# 3_6_1--esp32S3.net
KiCad netlist of a schematic drawn in EasyEDA Pro
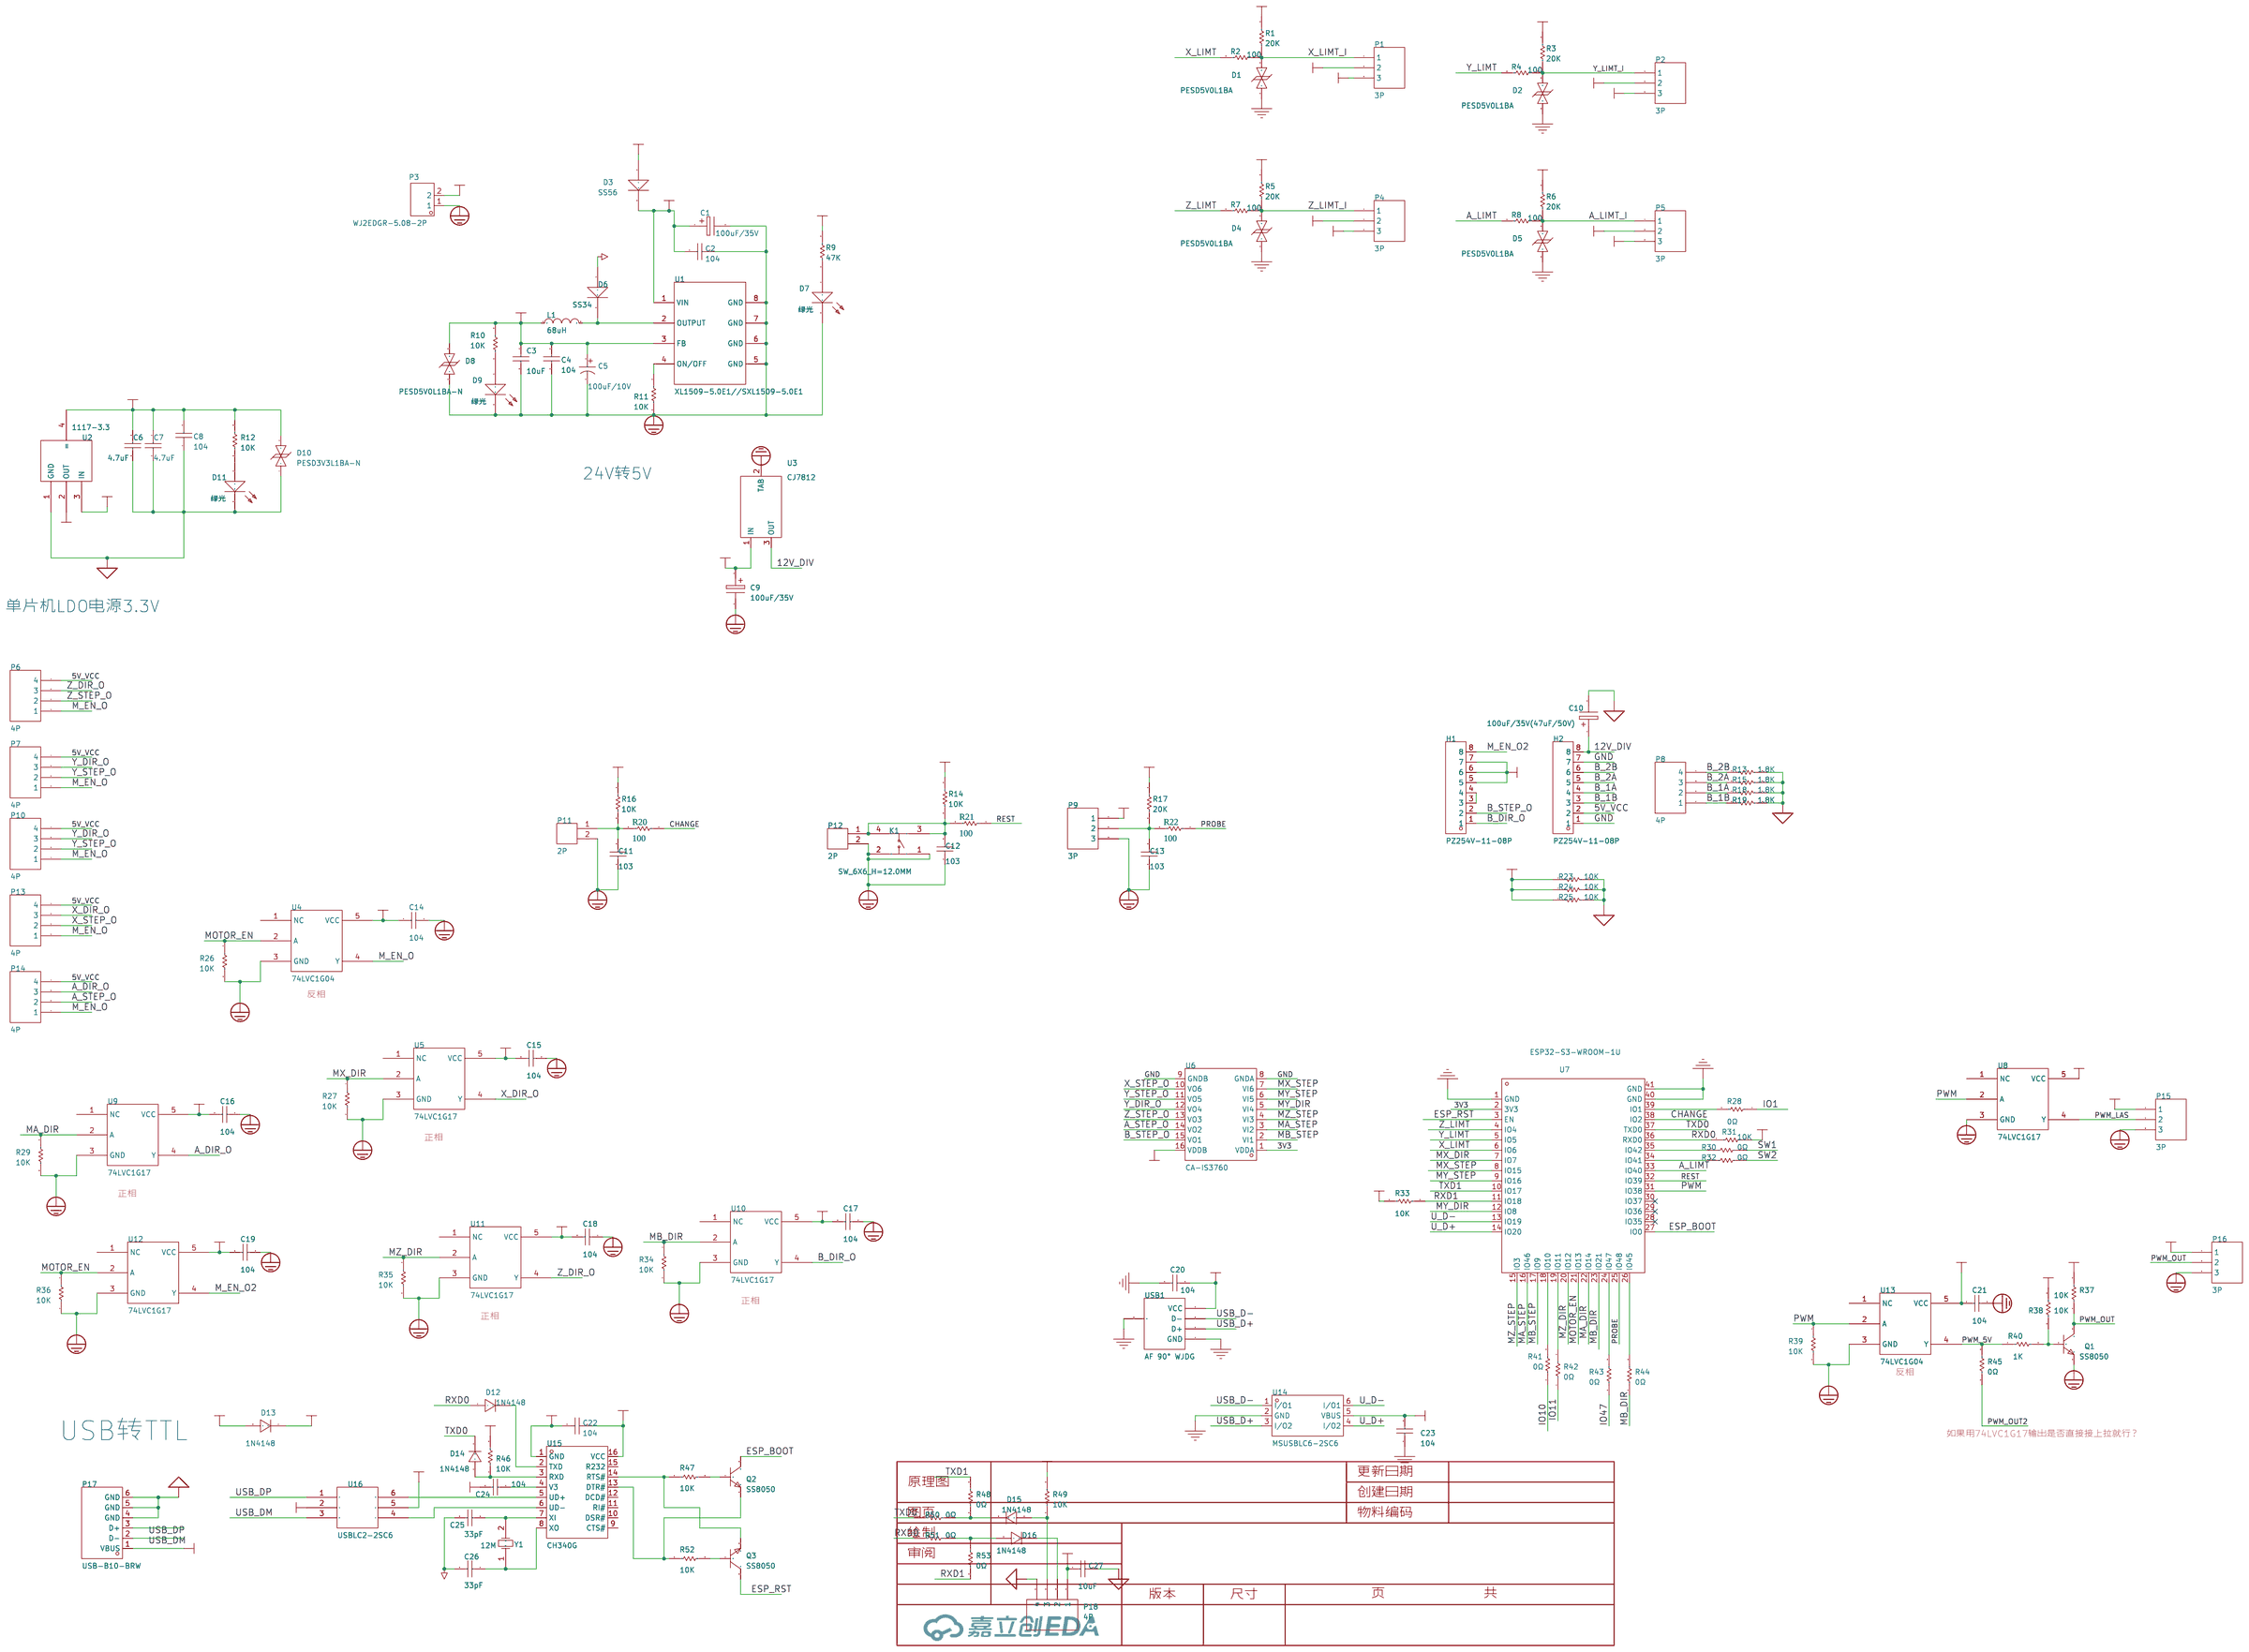
[diagram p0: schematic sheet]

(export (version "E")
  (design (tool "Eeschema 10.0.6"))
  (components
    (comp (ref "C1")
      (value "100uF/35V")
      (footprint "easyedapro:电解电容贴片10x10")
      (libsource (lib "easyedapro") (part "ELECTRO1"))
    )
    (comp (ref "C2")
      (value "104")
      (footprint "easyedapro:0603C")
      (description "Capacitor (Semiconductor SIM Model)")
      (libsource (lib "easyedapro") (part "Cap Semi"))
    )
    (comp (ref "C3") (value "10uF") (libsource (lib "") (part "CAP_1")))
    (comp (ref "C4")
      (value "104")
      (footprint "easyedapro:0603C")
      (description "Capacitor (Semiconductor SIM Model)")
      (libsource (lib "easyedapro") (part "Cap Semi"))
    )
    (comp (ref "C5")
      (value "100uF/10V")
      (footprint "easyedapro:CAP-SMD_BD5.0-L5.3-W5.3-RD")
      (fields (field (name "Manufacturer Part") "CS1A101M-CRD54") (field (name "Manufacturer") "ST(先科)"))
      (libsource (lib "easyedapro") (part "CS1A101M-CRD54"))
    )
    (comp (ref "C6") (value "4.7uF") (libsource (lib "") (part "CAP_1")))
    (comp (ref "C7") (value "4.7uF") (libsource (lib "") (part "CAP_1")))
    (comp (ref "C8")
      (value "104")
      (footprint "easyedapro:0603C")
      (description "Capacitor (Semiconductor SIM Model)")
      (libsource (lib "easyedapro") (part "Cap Semi"))
    )
    (comp (ref "C9")
      (value "100uF/35V")
      (footprint "easyedapro:电解电容贴片10x10")
      (libsource (lib "easyedapro") (part "ELECTRO1"))
    )
    (comp (ref "C10")
      (value "100uF/35V(47uF/50V)")
      (footprint "easyedapro:电解电容贴片10x10")
      (libsource (lib "easyedapro") (part "ELECTRO1"))
    )
    (comp (ref "C11") (value "103") (footprint "easyedapro:11") (libsource (lib "easyedapro") (part "CAP")))
    (comp (ref "C12") (value "103") (footprint "easyedapro:11") (libsource (lib "easyedapro") (part "CAP")))
    (comp (ref "C13") (value "103") (footprint "easyedapro:11") (libsource (lib "easyedapro") (part "CAP")))
    (comp (ref "C14")
      (value "104")
      (footprint "easyedapro:0603C")
      (description "Capacitor (Semiconductor SIM Model)")
      (libsource (lib "easyedapro") (part "Cap Semi"))
    )
    (comp (ref "C15")
      (value "104")
      (footprint "easyedapro:0603C")
      (description "Capacitor (Semiconductor SIM Model)")
      (libsource (lib "easyedapro") (part "Cap Semi"))
    )
    (comp (ref "C16")
      (value "104")
      (footprint "easyedapro:0603C")
      (description "Capacitor (Semiconductor SIM Model)")
      (libsource (lib "easyedapro") (part "Cap Semi"))
    )
    (comp (ref "C17")
      (value "104")
      (footprint "easyedapro:0603C")
      (description "Capacitor (Semiconductor SIM Model)")
      (libsource (lib "easyedapro") (part "Cap Semi"))
    )
    (comp (ref "C18")
      (value "104")
      (footprint "easyedapro:0603C")
      (description "Capacitor (Semiconductor SIM Model)")
      (libsource (lib "easyedapro") (part "Cap Semi"))
    )
    (comp (ref "C19")
      (value "104")
      (footprint "easyedapro:0603C")
      (description "Capacitor (Semiconductor SIM Model)")
      (libsource (lib "easyedapro") (part "Cap Semi"))
    )
    (comp (ref "C20")
      (value "104")
      (footprint "easyedapro:0603C")
      (description "Capacitor (Semiconductor SIM Model)")
      (libsource (lib "easyedapro") (part "Cap Semi"))
    )
    (comp (ref "C21")
      (value "104")
      (footprint "easyedapro:0603C")
      (description "Capacitor (Semiconductor SIM Model)")
      (libsource (lib "easyedapro") (part "Cap Semi"))
    )
    (comp (ref "C22")
      (value "104")
      (footprint "easyedapro:0603C")
      (description "Capacitor (Semiconductor SIM Model)")
      (libsource (lib "easyedapro") (part "Cap Semi"))
    )
    (comp (ref "C23")
      (value "104")
      (footprint "easyedapro:0603C")
      (description "Capacitor (Semiconductor SIM Model)")
      (libsource (lib "easyedapro") (part "Cap Semi"))
    )
    (comp (ref "C24")
      (value "104")
      (footprint "easyedapro:0603C")
      (description "Capacitor (Semiconductor SIM Model)")
      (libsource (lib "easyedapro") (part "Cap Semi"))
    )
    (comp (ref "C25")
      (value "18pF")
      (footprint "easyedapro:0603C")
      (description "Capacitor (Semiconductor SIM Model)")
      (libsource (lib "easyedapro") (part "Cap Semi"))
    )
    (comp (ref "C26")
      (value "18pF")
      (footprint "easyedapro:0603C")
      (description "Capacitor (Semiconductor SIM Model)")
      (libsource (lib "easyedapro") (part "Cap Semi"))
    )
    (comp (ref "C27") (value "10uF") (libsource (lib "") (part "CAP_1")))
    (comp (ref "D1")
      (value "PESD5V0L1BA")
      (footprint "easyedapro:SOD-523_L1.2-W0.8-LS1.6-BI")
      (description "极性:Bidirectional;反向关断电压（典型值）:5V (Max);击穿电压（最小值）:6V;箝位电压:15V;峰值脉冲电流（10/1000us）:5A (8/20us);")
      (fields (field (name "Manufacturer") "BORN伯恩半导体"))
      (libsource (lib "easyedapro") (part "PESD5V0S1BBN"))
    )
    (comp (ref "D2")
      (value "PESD5V0L1BA")
      (footprint "easyedapro:SOD-523_L1.2-W0.8-LS1.6-BI")
      (description "极性:Bidirectional;反向关断电压（典型值）:5V (Max);击穿电压（最小值）:6V;箝位电压:15V;峰值脉冲电流（10/1000us）:5A (8/20us);")
      (fields (field (name "Manufacturer") "BORN伯恩半导体"))
      (libsource (lib "easyedapro") (part "PESD5V0S1BBN"))
    )
    (comp (ref "D3") (value "SS56") (footprint "easyedapro:SMA") (libsource (lib "") (part "1N4148_1")))
    (comp (ref "D4")
      (value "PESD5V0L1BA")
      (footprint "easyedapro:SOD-523_L1.2-W0.8-LS1.6-BI")
      (description "极性:Bidirectional;反向关断电压（典型值）:5V (Max);击穿电压（最小值）:6V;箝位电压:15V;峰值脉冲电流（10/1000us）:5A (8/20us);")
      (fields (field (name "Manufacturer") "BORN伯恩半导体"))
      (libsource (lib "easyedapro") (part "PESD5V0S1BBN"))
    )
    (comp (ref "D5")
      (value "PESD5V0L1BA")
      (footprint "easyedapro:SOD-523_L1.2-W0.8-LS1.6-BI")
      (description "极性:Bidirectional;反向关断电压（典型值）:5V (Max);击穿电压（最小值）:6V;箝位电压:15V;峰值脉冲电流（10/1000us）:5A (8/20us);")
      (fields (field (name "Manufacturer") "BORN伯恩半导体"))
      (libsource (lib "easyedapro") (part "PESD5V0S1BBN"))
    )
    (comp (ref "D6") (value "SS34") (libsource (lib "easyedapro") (part "1N4148")))
    (comp (ref "D7")
      (value "绿光")
      (footprint "easyedapro:0603LED")
      (libsource (lib "easyedapro") (part "LED"))
    )
    (comp (ref "D8")
      (value "PESD5V0L1BA-N")
      (footprint "easyedapro:SOD-523_L1.2-W0.8-LS1.6-BI")
      (description "极性:Bidirectional;反向关断电压（典型值）:5V (Max);击穿电压（最小值）:6V;箝位电压:15V;峰值脉冲电流（10/1000us）:5A (8/20us);")
      (fields (field (name "Manufacturer") "BORN伯恩半导体"))
      (libsource (lib "easyedapro") (part "PESD5V0S1BBN"))
    )
    (comp (ref "D9")
      (value "绿光")
      (footprint "easyedapro:0603LED")
      (libsource (lib "easyedapro") (part "LED"))
    )
    (comp (ref "D10")
      (value "PESD3V3L1BA-N")
      (footprint "easyedapro:SOD-523_L1.2-W0.8-LS1.6-BI")
      (description "极性:Bidirectional;反向关断电压（典型值）:5V (Max);击穿电压（最小值）:6V;箝位电压:15V;峰值脉冲电流（10/1000us）:5A (8/20us);")
      (fields (field (name "Manufacturer") "BORN伯恩半导体"))
      (libsource (lib "easyedapro") (part "PESD5V0S1BBN"))
    )
    (comp (ref "D11")
      (value "绿光")
      (footprint "easyedapro:0603LED")
      (libsource (lib "easyedapro") (part "LED"))
    )
    (comp (ref "D12")
      (value "1N4148")
      (footprint "easyedapro:SOD-123_L2.8-W1.8-LS3.7-RD")
      (fields (field (name "Manufacturer") "MCC(美微科)"))
      (libsource (lib "easyedapro") (part "1N4148W-TP"))
    )
    (comp (ref "D13")
      (value "1N4148")
      (footprint "easyedapro:SOD-123_L2.8-W1.8-LS3.7-RD")
      (fields (field (name "Manufacturer") "MCC(美微科)"))
      (libsource (lib "easyedapro") (part "1N4148W-TP"))
    )
    (comp (ref "D14")
      (value "1N4148")
      (footprint "easyedapro:SOD-123_L2.8-W1.8-LS3.7-RD")
      (fields (field (name "Manufacturer") "MCC(美微科)"))
      (libsource (lib "easyedapro") (part "1N4148W-TP"))
    )
    (comp (ref "D15")
      (value "1N4148")
      (footprint "easyedapro:SOD-123_L2.8-W1.8-LS3.7-RD")
      (fields (field (name "Manufacturer") "MCC(美微科)"))
      (libsource (lib "easyedapro") (part "1N4148W-TP"))
    )
    (comp (ref "D16")
      (value "1N4148")
      (footprint "easyedapro:SOD-123_L2.8-W1.8-LS3.7-RD")
      (fields (field (name "Manufacturer") "MCC(美微科)"))
      (libsource (lib "easyedapro") (part "1N4148W-TP"))
    )
    (comp (ref "H1")
      (value "PZ254V-11-08P")
      (footprint "easyedapro:HDR-TH_8P-P2.54-V-M")
      (fields (field (name "Manufacturer") "XFCN(兴飞)"))
      (libsource (lib "easyedapro") (part "PZ254V-11-08P"))
    )
    (comp (ref "H2")
      (value "PZ254V-11-08P")
      (footprint "easyedapro:HDR-TH_8P-P2.54-V-M")
      (fields (field (name "Manufacturer") "XFCN(兴飞)"))
      (libsource (lib "easyedapro") (part "PZ254V-11-08P"))
    )
    (comp (ref "K1")
      (value "SW_6X6_H=12.0MM")
      (footprint "easyedapro:KEY-SMD_4P-L6.0-W6.0-P4.50-LS9.0")
      (libsource (lib "easyedapro") (part "SW_6X6_H=12.0MM"))
    )
    (comp (ref "L1")
      (value "68uH")
      (footprint "easyedapro:IND-SMD_L7.0-W7.0_SMDRI74-330MT")
      (description "电感值:33uH;精度:±20%;额定电流:960mA;饱和电流(Isat):1.8A;类型:屏蔽电感;")
      (fields (field (name "Manufacturer Part") "SMDRI74-330MT") (field (name "Manufacturer") "SXN(顺翔诺)"))
      (libsource (lib "easyedapro") (part "SMDRI74-330MT"))
    )
    (comp (ref "P1")
      (value "3P")
      (footprint "easyedapro:HDR1X3_CON")
      (libsource (lib "easyedapro") (part "3P"))
    )
    (comp (ref "P2")
      (value "3P")
      (footprint "easyedapro:HDR1X3_CON")
      (libsource (lib "easyedapro") (part "3P"))
    )
    (comp (ref "P3")
      (value "WJ2EDGR-5.08-2P")
      (footprint "easyedapro:CONN-TH_WJ2EDGR-5.08-2P")
      (description "每排PIN数:2;安装方式:弯针;排数:1;间距:5.08mm;连接器类型:板端/插座-开口;")
      (fields (field (name "Manufacturer") "KANGNEX(康奈克斯电气)"))
      (libsource (lib "easyedapro") (part "WJ2EDGR-5.08-2P"))
    )
    (comp (ref "P4")
      (value "3P")
      (footprint "easyedapro:HDR1X3_CON")
      (libsource (lib "easyedapro") (part "3P"))
    )
    (comp (ref "P5")
      (value "3P")
      (footprint "easyedapro:HDR1X3_CON")
      (libsource (lib "easyedapro") (part "3P"))
    )
    (comp (ref "P6")
      (value "4P")
      (footprint "easyedapro:HDR1X4_CON")
      (libsource (lib "easyedapro") (part "4P"))
    )
    (comp (ref "P7")
      (value "4P")
      (footprint "easyedapro:HDR1X4_CON")
      (libsource (lib "easyedapro") (part "4P"))
    )
    (comp (ref "P8")
      (value "4P")
      (footprint "easyedapro:HDR1X4_CON")
      (libsource (lib "easyedapro") (part "4P"))
    )
    (comp (ref "P9")
      (value "3P")
      (footprint "easyedapro:HDR1X3_CON")
      (libsource (lib "easyedapro") (part "3P"))
    )
    (comp (ref "P10")
      (value "4P")
      (footprint "easyedapro:HDR1X4_CON")
      (libsource (lib "easyedapro") (part "4P"))
    )
    (comp (ref "P11") (value "2P") (libsource (lib "easyedapro") (part "2P")))
    (comp (ref "P12") (value "2P") (libsource (lib "easyedapro") (part "2P")))
    (comp (ref "P13")
      (value "4P")
      (footprint "easyedapro:HDR1X4_CON")
      (libsource (lib "easyedapro") (part "4P"))
    )
    (comp (ref "P14")
      (value "4P")
      (footprint "easyedapro:HDR1X4_CON")
      (libsource (lib "easyedapro") (part "4P"))
    )
    (comp (ref "P15")
      (value "3P")
      (footprint "easyedapro:HDR1X3_CON")
      (libsource (lib "easyedapro") (part "3P"))
    )
    (comp (ref "P16")
      (value "3P")
      (footprint "easyedapro:HDR1X3_CON")
      (libsource (lib "easyedapro") (part "3P"))
    )
    (comp (ref "P17")
      (value "USB-B10-BRW")
      (footprint "easyedapro:USB-B-TH_USB-B10-BRW")
      (fields (field (name "Manufacturer") "XUNPU(讯普)"))
      (libsource (lib "easyedapro") (part "USB-B10-BRW"))
    )
    (comp (ref "P18")
      (value "4P")
      (footprint "easyedapro:HDR1X4_CON")
      (libsource (lib "easyedapro") (part "4P"))
    )
    (comp (ref "Q1")
      (value "SS8050")
      (footprint "easyedapro:SOT-23-3_L2.9-W1.3-P1.90-LS2.4-BR")
      (fields (field (name "Manufacturer") "CJ（江苏长电/长晶）"))
      (libsource (lib "easyedapro") (part "SS8050_C2150"))
    )
    (comp (ref "Q2")
      (value "SS8050")
      (footprint "easyedapro:SOT-23-3_L2.9-W1.3-P1.90-LS2.4-BR")
      (fields (field (name "Manufacturer") "Doeshare(德芯)"))
      (libsource (lib "easyedapro") (part "SS8050_C2931717"))
    )
    (comp (ref "Q3")
      (value "SS8050")
      (footprint "easyedapro:SOT-23-3_L2.9-W1.3-P1.90-LS2.4-BR")
      (fields (field (name "Manufacturer") "Doeshare(德芯)"))
      (libsource (lib "easyedapro") (part "SS8050_C2931717"))
    )
    (comp (ref "R1")
      (value "20K")
      (footprint "easyedapro:10")
      (description "Resistor")
      (libsource (lib "easyedapro") (part "RES"))
    )
    (comp (ref "R2")
      (value "100")
      (footprint "easyedapro:10")
      (description "Resistor")
      (libsource (lib "easyedapro") (part "RES"))
    )
    (comp (ref "R3")
      (value "20K")
      (footprint "easyedapro:10")
      (description "Resistor")
      (libsource (lib "easyedapro") (part "RES"))
    )
    (comp (ref "R4")
      (value "100")
      (footprint "easyedapro:10")
      (description "Resistor")
      (libsource (lib "easyedapro") (part "RES"))
    )
    (comp (ref "R5")
      (value "20K")
      (footprint "easyedapro:10")
      (description "Resistor")
      (libsource (lib "easyedapro") (part "RES"))
    )
    (comp (ref "R6")
      (value "20K")
      (footprint "easyedapro:10")
      (description "Resistor")
      (libsource (lib "easyedapro") (part "RES"))
    )
    (comp (ref "R7")
      (value "100")
      (footprint "easyedapro:10")
      (description "Resistor")
      (libsource (lib "easyedapro") (part "RES"))
    )
    (comp (ref "R8")
      (value "100")
      (footprint "easyedapro:10")
      (description "Resistor")
      (libsource (lib "easyedapro") (part "RES"))
    )
    (comp (ref "R9")
      (value "47K")
      (footprint "easyedapro:0603R")
      (description "Resistor")
      (libsource (lib "easyedapro") (part "RES"))
    )
    (comp (ref "R10")
      (value "10K")
      (footprint "easyedapro:0603R")
      (description "Resistor")
      (libsource (lib "easyedapro") (part "RES"))
    )
    (comp (ref "R11")
      (value "10K")
      (footprint "easyedapro:0603R")
      (description "Resistor")
      (libsource (lib "easyedapro") (part "RES"))
    )
    (comp (ref "R12")
      (value "10K")
      (footprint "easyedapro:0603R")
      (description "Resistor")
      (libsource (lib "easyedapro") (part "RES"))
    )
    (comp (ref "R13")
      (value "10K")
      (footprint "easyedapro:0603R")
      (description "Resistor")
      (libsource (lib "easyedapro") (part "10K"))
    )
    (comp (ref "R14")
      (value "10K")
      (footprint "easyedapro:0603R")
      (description "Resistor")
      (libsource (lib "easyedapro") (part "RES"))
    )
    (comp (ref "R15")
      (value "10K")
      (footprint "easyedapro:0603R")
      (description "Resistor")
      (libsource (lib "easyedapro") (part "10K"))
    )
    (comp (ref "R16")
      (value "10K")
      (footprint "easyedapro:0603R")
      (description "Resistor")
      (libsource (lib "easyedapro") (part "RES"))
    )
    (comp (ref "R17")
      (value "10K")
      (footprint "easyedapro:0603R")
      (description "Resistor")
      (libsource (lib "easyedapro") (part "RES"))
    )
    (comp (ref "R18")
      (value "10K")
      (footprint "easyedapro:0603R")
      (description "Resistor")
      (libsource (lib "easyedapro") (part "10K"))
    )
    (comp (ref "R19")
      (value "10K")
      (footprint "easyedapro:0603R")
      (description "Resistor")
      (libsource (lib "easyedapro") (part "10K"))
    )
    (comp (ref "R20")
      (value "100")
      (description "Resistor")
      (fields (field (name "Publisher") "Altium Limited"))
      (libsource (lib "") (part "RES_1"))
    )
    (comp (ref "R21")
      (value "100")
      (description "Resistor")
      (fields (field (name "Publisher") "Altium Limited"))
      (libsource (lib "") (part "RES_1"))
    )
    (comp (ref "R22")
      (value "100")
      (description "Resistor")
      (fields (field (name "Publisher") "Altium Limited"))
      (libsource (lib "") (part "RES_1"))
    )
    (comp (ref "R23")
      (value "10K")
      (footprint "easyedapro:0603R")
      (description "Resistor")
      (libsource (lib "easyedapro") (part "10K"))
    )
    (comp (ref "R24")
      (value "10K")
      (footprint "easyedapro:0603R")
      (description "Resistor")
      (libsource (lib "easyedapro") (part "10K"))
    )
    (comp (ref "R25")
      (value "10K")
      (footprint "easyedapro:0603R")
      (description "Resistor")
      (libsource (lib "easyedapro") (part "10K"))
    )
    (comp (ref "R26")
      (value "10K")
      (description "Resistor")
      (fields (field (name "Publisher") "Altium Limited"))
      (libsource (lib "") (part "RES_1"))
    )
    (comp (ref "R27")
      (value "10K")
      (description "Resistor")
      (fields (field (name "Publisher") "Altium Limited"))
      (libsource (lib "") (part "RES_1"))
    )
    (comp (ref "R28")
      (value "0Ω")
      (description "Resistor")
      (fields (field (name "Publisher") "Altium Limited"))
      (libsource (lib "") (part "RES_1"))
    )
    (comp (ref "R29")
      (value "10K")
      (description "Resistor")
      (fields (field (name "Publisher") "Altium Limited"))
      (libsource (lib "") (part "RES_1"))
    )
    (comp (ref "R30")
      (value "0Ω")
      (description "Resistor")
      (fields (field (name "Publisher") "Altium Limited"))
      (libsource (lib "") (part "RES_1"))
    )
    (comp (ref "R31")
      (value "10K")
      (footprint "easyedapro:0603R")
      (description "Resistor")
      (libsource (lib "easyedapro") (part "RES"))
    )
    (comp (ref "R32")
      (value "0Ω")
      (description "Resistor")
      (fields (field (name "Publisher") "Altium Limited"))
      (libsource (lib "") (part "RES_1"))
    )
    (comp (ref "R33")
      (value "10K")
      (footprint "easyedapro:0603R")
      (description "Resistor")
      (libsource (lib "easyedapro") (part "RES"))
    )
    (comp (ref "R34")
      (value "10K")
      (description "Resistor")
      (fields (field (name "Publisher") "Altium Limited"))
      (libsource (lib "") (part "RES_1"))
    )
    (comp (ref "R35")
      (value "10K")
      (description "Resistor")
      (fields (field (name "Publisher") "Altium Limited"))
      (libsource (lib "") (part "RES_1"))
    )
    (comp (ref "R36")
      (value "10K")
      (description "Resistor")
      (fields (field (name "Publisher") "Altium Limited"))
      (libsource (lib "") (part "RES_1"))
    )
    (comp (ref "R37")
      (value "10K")
      (description "Resistor")
      (fields (field (name "Publisher") "Altium Limited"))
      (libsource (lib "") (part "RES_1"))
    )
    (comp (ref "R38")
      (value "10K")
      (description "Resistor")
      (fields (field (name "Publisher") "Altium Limited"))
      (libsource (lib "") (part "RES_1"))
    )
    (comp (ref "R39")
      (value "10K")
      (description "Resistor")
      (fields (field (name "Publisher") "Altium Limited"))
      (libsource (lib "") (part "RES_1"))
    )
    (comp (ref "R40")
      (value "1K")
      (description "Resistor")
      (fields (field (name "Publisher") "Altium Limited"))
      (libsource (lib "") (part "RES_1"))
    )
    (comp (ref "R41")
      (value "0Ω")
      (description "Resistor")
      (fields (field (name "Publisher") "Altium Limited"))
      (libsource (lib "") (part "RES_1"))
    )
    (comp (ref "R42")
      (value "0Ω")
      (description "Resistor")
      (fields (field (name "Publisher") "Altium Limited"))
      (libsource (lib "") (part "RES_1"))
    )
    (comp (ref "R43")
      (value "0Ω")
      (description "Resistor")
      (fields (field (name "Publisher") "Altium Limited"))
      (libsource (lib "") (part "RES_1"))
    )
    (comp (ref "R44")
      (value "0Ω")
      (description "Resistor")
      (fields (field (name "Publisher") "Altium Limited"))
      (libsource (lib "") (part "RES_1"))
    )
    (comp (ref "R45")
      (value "0Ω")
      (description "Resistor")
      (fields (field (name "Publisher") "Altium Limited"))
      (libsource (lib "") (part "RES_1"))
    )
    (comp (ref "R46")
      (value "10K")
      (footprint "easyedapro:0603R")
      (description "Resistor")
      (libsource (lib "easyedapro") (part "RES"))
    )
    (comp (ref "R47")
      (value "10K")
      (footprint "easyedapro:0603R")
      (description "Resistor")
      (libsource (lib "easyedapro") (part "RES"))
    )
    (comp (ref "R48")
      (value "0Ω")
      (description "Resistor")
      (fields (field (name "Publisher") "Altium Limited"))
      (libsource (lib "") (part "RES_1"))
    )
    (comp (ref "R49")
      (value "10K")
      (footprint "easyedapro:0603R")
      (description "Resistor")
      (libsource (lib "easyedapro") (part "RES"))
    )
    (comp (ref "R50")
      (value "0Ω")
      (description "Resistor")
      (fields (field (name "Publisher") "Altium Limited"))
      (libsource (lib "") (part "RES_1"))
    )
    (comp (ref "R51")
      (value "0Ω")
      (description "Resistor")
      (fields (field (name "Publisher") "Altium Limited"))
      (libsource (lib "") (part "RES_1"))
    )
    (comp (ref "R52")
      (value "10K")
      (footprint "easyedapro:0603R")
      (description "Resistor")
      (libsource (lib "easyedapro") (part "RES"))
    )
    (comp (ref "R53")
      (value "0Ω")
      (description "Resistor")
      (fields (field (name "Publisher") "Altium Limited"))
      (libsource (lib "") (part "RES_1"))
    )
    (comp (ref "U1")
      (value "XL1509-5.0E1//SXL1509-5.0E1")
      (footprint "easyedapro:SOIC-8_L5.0-W4.0-P1.27-LS6.0-BL")
      (description "功能类型:降压型;同步整流:-;输出通道数:-;拓扑结构:-;输入电压:-;输出电流(最大值):-;开关频率:-;")
      (fields (field (name "Manufacturer") "XLSEMI(芯龙)"))
      (libsource (lib "easyedapro") (part "XL1509-5.0E1"))
    )
    (comp (ref "U2")
      (value "1117-3.3")
      (footprint "easyedapro:SOT-223")
      (libsource (lib "easyedapro") (part "LM1117"))
    )
    (comp (ref "U3")
      (value "CJ7812")
      (footprint "easyedapro:TO-263-2_L10.1-W9.1-P5.08-LS15.2-TL")
      (description "输出类型:固定;工作电压:35V;输出电压:12V;输出电流:1.5A;电源纹波抑制比(PSRR):71dB@(120Hz);输出极性:正极;")
      (fields (field (name "Manufacturer") "CJ(江苏长电/长晶)"))
      (libsource (lib "easyedapro") (part "CJ7812_C145151"))
    )
    (comp (ref "U4")
      (value "74LVC1G04")
      (footprint "easyedapro:SMD8")
      (libsource (lib "easyedapro") (part "74LVC1G04"))
    )
    (comp (ref "U5")
      (value "74LVC1G17")
      (footprint "easyedapro:SMD8")
      (libsource (lib "easyedapro") (part "74LVC1G04"))
    )
    (comp (ref "U6")
      (value "CA-IS3760")
      (footprint "easyedapro:SOIC-16_L9.9-W3.9-P1.27-LS6.0-BL")
      (fields (field (name "Manufacturer") "Chipanalog(川土微)"))
      (libsource (lib "easyedapro") (part "CA-IS3760HN"))
    )
    (comp (ref "U7")
      (value "ESP32-S3-WROOM-1U")
      (footprint "easyedapro:ESP32-S3-WROOM-1U")
      (fields
        (field (name "Manufacturer Part") "ESP32-S3-WROOM-1(N16R2)")
        (field (name "Manufacturer") "ESPRESSIF(----)")
      )
      (libsource (lib "easyedapro") (part "ESP32-S3-WROOM-1(N16R2)"))
    )
    (comp (ref "U8")
      (value "74LVC1G17")
      (footprint "easyedapro:SMD8")
      (libsource (lib "easyedapro") (part "74LVC1G04"))
    )
    (comp (ref "U9")
      (value "74LVC1G17")
      (footprint "easyedapro:SMD8")
      (libsource (lib "easyedapro") (part "74LVC1G04"))
    )
    (comp (ref "U10")
      (value "74LVC1G17")
      (footprint "easyedapro:SMD8")
      (libsource (lib "easyedapro") (part "74LVC1G04"))
    )
    (comp (ref "U11")
      (value "74LVC1G17")
      (footprint "easyedapro:SMD8")
      (libsource (lib "easyedapro") (part "74LVC1G04"))
    )
    (comp (ref "U12")
      (value "74LVC1G17")
      (footprint "easyedapro:SMD8")
      (libsource (lib "easyedapro") (part "74LVC1G04"))
    )
    (comp (ref "U13")
      (value "74LVC1G04")
      (footprint "easyedapro:SMD8")
      (libsource (lib "easyedapro") (part "74LVC1G04"))
    )
    (comp (ref "U14")
      (value "MSUSBLC6-2SC6")
      (footprint "easyedapro:SOT-23-6_L2.9-W1.6-P0.95-LS2.8-BL")
      (description "反向截止电压(Vrwm):5V;最大钳位电压:15V;峰值脉冲电流(Ipp)@10/1000us:6A;峰值脉冲功率(Ppp)@10/1000us:150W;击穿电压:9V;")
      (fields (field (name "Manufacturer") "MSKSEMI(美森科)"))
      (libsource (lib "easyedapro") (part "MSUSBLC6-2SC6"))
    )
    (comp (ref "U15")
      (value "CH340G")
      (footprint "easyedapro:SOIC-16_L9.9-W3.9-P1.27-LS6.0-BL")
      (description "应用功能:收发器;接口协议:USB 2.0;数据速率:2Mbps;")
      (fields (field (name "Manufacturer") "WCH(南京沁恒)"))
      (libsource (lib "easyedapro") (part "CH340G"))
    )
    (comp (ref "U16")
      (value "USBLC2-2SC6")
      (footprint "easyedapro:SOT-23-6")
      (libsource (lib "easyedapro") (part "DIP6"))
    )
    (comp (ref "USB1")
      (value "AF 90° WJDG")
      (footprint "easyedapro:USB-A-TH_AF-WJDG")
      (description "连接器类型:Type-A;标准:USB 2.0;公母:母;安装方式:弯插;触点数量:4P;端口数量:1;额定电流 - 电源:1.5A;工作温度范围:-25°C~+85°C;")
      (fields (field (name "Manufacturer") "SHOU HAN(首韩)"))
      (libsource (lib "easyedapro") (part "AF 90° WJDG"))
    )
    (comp (ref "Y1")
      (value "12M")
      (footprint "easyedapro:晶振贴片49SSMD")
      (description "Crystal Oscillator")
      (libsource (lib "easyedapro") (part "XTAL"))
    )
  )
  (nets
    (net (code "1") (name "/12V_DIV") (class "Default")
      (node (ref "C10") (pin "1") (pintype "unspecified"))
      (node (ref "H2") (pin "8") (pinfunction "8_8") (pintype "unspecified"))
      (node (ref "U3") (pin "3") (pinfunction "OUT_3") (pintype "unspecified"))
    )
    (net (code "2") (name "/A_DIR_O") (class "Default")
      (node (ref "P14") (pin "3") (pinfunction "3_3") (pintype "unspecified"))
      (node (ref "U9") (pin "4") (pinfunction "Y_4") (pintype "unspecified"))
    )
    (net (code "3") (name "/A_LIMT") (class "Default")
      (node (ref "R8") (pin "2") (pinfunction "2_2") (pintype "unspecified"))
      (node (ref "U7") (pin "33") (pinfunction "IO40_33") (pintype "unspecified"))
    )
    (net (code "4") (name "/A_LIMT_I") (class "Default")
      (node (ref "D5") (pin "2") (pinfunction "2_2") (pintype "input"))
      (node (ref "P5") (pin "1") (pinfunction "1_1") (pintype "unspecified"))
      (node (ref "R6") (pin "1") (pinfunction "1_1") (pintype "unspecified"))
      (node (ref "R8") (pin "1") (pinfunction "1_1") (pintype "unspecified"))
    )
    (net (code "5") (name "/A_STEP_O") (class "Default")
      (node (ref "P14") (pin "2") (pinfunction "2_2") (pintype "unspecified"))
      (node (ref "U6") (pin "14") (pinfunction "VO2_14") (pintype "unspecified"))
    )
    (net (code "6") (name "/B_1A") (class "Default")
      (node (ref "H2") (pin "4") (pinfunction "4_4") (pintype "unspecified"))
      (node (ref "P8") (pin "2") (pinfunction "2_2") (pintype "unspecified"))
      (node (ref "R18") (pin "1") (pinfunction "1_1") (pintype "unspecified"))
    )
    (net (code "7") (name "/B_1B") (class "Default")
      (node (ref "H2") (pin "3") (pinfunction "3_3") (pintype "unspecified"))
      (node (ref "P8") (pin "1") (pinfunction "1_1") (pintype "unspecified"))
      (node (ref "R19") (pin "1") (pinfunction "1_1") (pintype "unspecified"))
    )
    (net (code "8") (name "/B_2A") (class "Default")
      (node (ref "H2") (pin "5") (pinfunction "5_5") (pintype "unspecified"))
      (node (ref "P8") (pin "3") (pinfunction "3_3") (pintype "unspecified"))
      (node (ref "R15") (pin "1") (pinfunction "1_1") (pintype "unspecified"))
    )
    (net (code "9") (name "/B_2B") (class "Default")
      (node (ref "H2") (pin "6") (pinfunction "6_6") (pintype "unspecified"))
      (node (ref "P8") (pin "4") (pinfunction "4_4") (pintype "unspecified"))
      (node (ref "R13") (pin "1") (pinfunction "1_1") (pintype "unspecified"))
    )
    (net (code "10") (name "/B_DIR_O") (class "Default")
      (node (ref "H1") (pin "1") (pinfunction "1_1") (pintype "unspecified"))
      (node (ref "U10") (pin "4") (pinfunction "Y_4") (pintype "unspecified"))
    )
    (net (code "11") (name "/B_STEP_O") (class "Default")
      (node (ref "H1") (pin "2") (pinfunction "2_2") (pintype "unspecified"))
      (node (ref "U6") (pin "15") (pinfunction "VO1_15") (pintype "unspecified"))
    )
    (net (code "12") (name "/CHANGE") (class "Default")
      (node (ref "R20") (pin "1") (pinfunction "1_1") (pintype "input"))
      (node (ref "U7") (pin "38") (pinfunction "IO2_38") (pintype "unspecified"))
    )
    (net (code "13") (name "/ESP_BOOT") (class "Default")
      (node (ref "Q2") (pin "3") (pinfunction "C_3") (pintype "unspecified"))
      (node (ref "U7") (pin "27") (pinfunction "IO0_27") (pintype "unspecified"))
    )
    (net (code "14") (name "/ESP_RST") (class "Default")
      (node (ref "Q3") (pin "3") (pinfunction "C_3") (pintype "unspecified"))
      (node (ref "U7") (pin "3") (pinfunction "EN_3") (pintype "unspecified"))
    )
    (net (code "15") (name "/IO1") (class "Default")
      (node (ref "R28") (pin "1") (pinfunction "1_1") (pintype "input"))
    )
    (net (code "16") (name "/IO10") (class "Default")
      (node (ref "R41") (pin "1") (pinfunction "1_1") (pintype "input"))
    )
    (net (code "17") (name "/IO11") (class "Default")
      (node (ref "R42") (pin "1") (pinfunction "1_1") (pintype "input"))
    )
    (net (code "18") (name "/IO47") (class "Default")
      (node (ref "R43") (pin "1") (pinfunction "1_1") (pintype "input"))
    )
    (net (code "19") (name "/MA_DIR") (class "Default")
      (node (ref "R29") (pin "1") (pinfunction "1_1") (pintype "input"))
      (node (ref "U7") (pin "22") (pinfunction "IO14_22") (pintype "unspecified"))
      (node (ref "U9") (pin "2") (pinfunction "A_2") (pintype "unspecified"))
    )
    (net (code "20") (name "/MA_STEP") (class "Default")
      (node (ref "U6") (pin "3") (pinfunction "VI2_3") (pintype "unspecified"))
      (node (ref "U7") (pin "16") (pinfunction "IO46_16") (pintype "unspecified"))
    )
    (net (code "21") (name "/MB_DIR") (class "Default")
      (node (ref "R34") (pin "1") (pinfunction "1_1") (pintype "input"))
      (node (ref "R44") (pin "1") (pinfunction "1_1") (pintype "input"))
      (node (ref "U10") (pin "2") (pinfunction "A_2") (pintype "unspecified"))
      (node (ref "U7") (pin "23") (pinfunction "IO21_23") (pintype "unspecified"))
    )
    (net (code "22") (name "/MB_STEP") (class "Default")
      (node (ref "U6") (pin "2") (pinfunction "VI1_2") (pintype "unspecified"))
      (node (ref "U7") (pin "17") (pinfunction "IO9_17") (pintype "unspecified"))
    )
    (net (code "23") (name "/MOTOR_EN") (class "Default")
      (node (ref "R26") (pin "1") (pinfunction "1_1") (pintype "input"))
      (node (ref "R36") (pin "1") (pinfunction "1_1") (pintype "input"))
      (node (ref "U12") (pin "2") (pinfunction "A_2") (pintype "unspecified"))
      (node (ref "U4") (pin "2") (pinfunction "A_2") (pintype "unspecified"))
      (node (ref "U7") (pin "21") (pinfunction "IO13_21") (pintype "unspecified"))
    )
    (net (code "24") (name "/MX_DIR") (class "Default")
      (node (ref "R27") (pin "1") (pinfunction "1_1") (pintype "input"))
      (node (ref "U5") (pin "2") (pinfunction "A_2") (pintype "unspecified"))
      (node (ref "U7") (pin "7") (pinfunction "IO7_7") (pintype "unspecified"))
    )
    (net (code "25") (name "/MX_STEP") (class "Default")
      (node (ref "U6") (pin "7") (pinfunction "VI6_7") (pintype "unspecified"))
      (node (ref "U7") (pin "8") (pinfunction "IO15_8") (pintype "unspecified"))
    )
    (net (code "26") (name "/MY_DIR") (class "Default")
      (node (ref "U6") (pin "5") (pinfunction "VI4_5") (pintype "unspecified"))
      (node (ref "U7") (pin "12") (pinfunction "IO8_12") (pintype "unspecified"))
    )
    (net (code "27") (name "/MY_STEP") (class "Default")
      (node (ref "U6") (pin "6") (pinfunction "VI5_6") (pintype "unspecified"))
      (node (ref "U7") (pin "9") (pinfunction "IO16_9") (pintype "unspecified"))
    )
    (net (code "28") (name "/MZ_DIR") (class "Default")
      (node (ref "R35") (pin "1") (pinfunction "1_1") (pintype "input"))
      (node (ref "U11") (pin "2") (pinfunction "A_2") (pintype "unspecified"))
      (node (ref "U7") (pin "20") (pinfunction "IO12_20") (pintype "unspecified"))
    )
    (net (code "29") (name "/MZ_STEP") (class "Default")
      (node (ref "U6") (pin "4") (pinfunction "VI3_4") (pintype "unspecified"))
      (node (ref "U7") (pin "15") (pinfunction "IO3_15") (pintype "unspecified"))
    )
    (net (code "30") (name "/M_EN_O") (class "Default")
      (node (ref "P10") (pin "1") (pinfunction "1_1") (pintype "unspecified"))
      (node (ref "P13") (pin "1") (pinfunction "1_1") (pintype "unspecified"))
      (node (ref "P14") (pin "1") (pinfunction "1_1") (pintype "unspecified"))
      (node (ref "P6") (pin "1") (pinfunction "1_1") (pintype "unspecified"))
      (node (ref "P7") (pin "1") (pinfunction "1_1") (pintype "unspecified"))
      (node (ref "U4") (pin "4") (pinfunction "Y_4") (pintype "unspecified"))
    )
    (net (code "31") (name "/M_EN_O2") (class "Default")
      (node (ref "H1") (pin "8") (pinfunction "8_8") (pintype "unspecified"))
      (node (ref "U12") (pin "4") (pinfunction "Y_4") (pintype "unspecified"))
    )
    (net (code "32") (name "/PROBE") (class "Default")
      (node (ref "R22") (pin "1") (pinfunction "1_1") (pintype "input"))
      (node (ref "U7") (pin "25") (pinfunction "IO48_25") (pintype "unspecified"))
    )
    (net (code "33") (name "/PWM") (class "Default")
      (node (ref "R39") (pin "1") (pinfunction "1_1") (pintype "input"))
      (node (ref "U13") (pin "2") (pinfunction "A_2") (pintype "unspecified"))
      (node (ref "U7") (pin "31") (pinfunction "IO38_31") (pintype "unspecified"))
      (node (ref "U8") (pin "2") (pinfunction "A_2") (pintype "unspecified"))
    )
    (net (code "34") (name "/PWM_5V") (class "Default")
      (node (ref "R40") (pin "1") (pinfunction "1_1") (pintype "input"))
      (node (ref "R45") (pin "2") (pinfunction "2_2") (pintype "input"))
      (node (ref "U13") (pin "4") (pinfunction "Y_4") (pintype "unspecified"))
    )
    (net (code "35") (name "/PWM_LAS") (class "Default")
      (node (ref "P15") (pin "2") (pinfunction "2_2") (pintype "unspecified"))
      (node (ref "U8") (pin "4") (pinfunction "Y_4") (pintype "unspecified"))
    )
    (net (code "36") (name "/PWM_OUT") (class "Default")
      (node (ref "P16") (pin "2") (pinfunction "2_2") (pintype "unspecified"))
      (node (ref "Q1") (pin "3") (pinfunction "C_3") (pintype "input"))
      (node (ref "R37") (pin "1") (pinfunction "1_1") (pintype "input"))
    )
    (net (code "37") (name "/PWM_OUT2") (class "Default")
      (node (ref "R45") (pin "1") (pinfunction "1_1") (pintype "input"))
    )
    (net (code "38") (name "/REST") (class "Default")
      (node (ref "R21") (pin "1") (pinfunction "1_1") (pintype "input"))
      (node (ref "U7") (pin "32") (pinfunction "IO39_32") (pintype "unspecified"))
    )
    (net (code "39") (name "/RXD0") (class "Default")
      (node (ref "D12") (pin "2") (pinfunction "A_2") (pintype "input"))
      (node (ref "R31") (pin "2") (pinfunction "2_2") (pintype "unspecified"))
      (node (ref "R51") (pin "1") (pinfunction "1_1") (pintype "input"))
      (node (ref "U7") (pin "36") (pinfunction "RXD0_36") (pintype "unspecified"))
    )
    (net (code "40") (name "/RXD1") (class "Default")
      (node (ref "R33") (pin "1") (pinfunction "1_1") (pintype "unspecified"))
      (node (ref "R53") (pin "1") (pinfunction "1_1") (pintype "input"))
      (node (ref "U7") (pin "11") (pinfunction "IO18_11") (pintype "unspecified"))
    )
    (net (code "41") (name "/SW1") (class "Default")
      (node (ref "R30") (pin "1") (pinfunction "1_1") (pintype "input"))
    )
    (net (code "42") (name "/SW2") (class "Default")
      (node (ref "R32") (pin "1") (pinfunction "1_1") (pintype "input"))
    )
    (net (code "43") (name "/TXD0") (class "Default")
      (node (ref "D14") (pin "1") (pinfunction "c_1") (pintype "input"))
      (node (ref "R50") (pin "1") (pinfunction "1_1") (pintype "input"))
      (node (ref "U7") (pin "37") (pinfunction "TXD0_37") (pintype "unspecified"))
    )
    (net (code "44") (name "/TXD1") (class "Default")
      (node (ref "R48") (pin "2") (pinfunction "2_2") (pintype "input"))
      (node (ref "U7") (pin "10") (pinfunction "IO17_10") (pintype "unspecified"))
    )
    (net (code "45") (name "/USB_D+") (class "Default")
      (node (ref "U14") (pin "3") (pinfunction "I/O2_3") (pintype "unspecified"))
      (node (ref "USB1") (pin "3") (pinfunction "D+_3") (pintype "input"))
    )
    (net (code "46") (name "/USB_D-") (class "Default")
      (node (ref "U14") (pin "1") (pinfunction "I/O1_1") (pintype "unspecified"))
      (node (ref "USB1") (pin "2") (pinfunction "D-_2") (pintype "input"))
    )
    (net (code "47") (name "/USB_DM") (class "Default")
      (node (ref "P17") (pin "2") (pinfunction "D-_2") (pintype "unspecified"))
      (node (ref "U16") (pin "3") (pinfunction "3_3") (pintype "unspecified"))
    )
    (net (code "48") (name "/USB_DP") (class "Default")
      (node (ref "P17") (pin "3") (pinfunction "D+_3") (pintype "unspecified"))
      (node (ref "U16") (pin "1") (pinfunction "1_1") (pintype "unspecified"))
    )
    (net (code "49") (name "/U_D+") (class "Default")
      (node (ref "U14") (pin "4") (pinfunction "I/O2_4") (pintype "unspecified"))
      (node (ref "U7") (pin "14") (pinfunction "IO20_14") (pintype "unspecified"))
    )
    (net (code "50") (name "/U_D-") (class "Default")
      (node (ref "U14") (pin "6") (pinfunction "I/O1_6") (pintype "unspecified"))
      (node (ref "U7") (pin "13") (pinfunction "IO19_13") (pintype "unspecified"))
    )
    (net (code "51") (name "/X_DIR_O") (class "Default")
      (node (ref "P13") (pin "3") (pinfunction "3_3") (pintype "unspecified"))
      (node (ref "U5") (pin "4") (pinfunction "Y_4") (pintype "unspecified"))
    )
    (net (code "52") (name "/X_LIMT") (class "Default")
      (node (ref "R2") (pin "2") (pinfunction "2_2") (pintype "unspecified"))
      (node (ref "U7") (pin "6") (pinfunction "IO6_6") (pintype "unspecified"))
    )
    (net (code "53") (name "/X_LIMT_I") (class "Default")
      (node (ref "D1") (pin "2") (pinfunction "2_2") (pintype "input"))
      (node (ref "P1") (pin "1") (pinfunction "1_1") (pintype "unspecified"))
      (node (ref "R1") (pin "1") (pinfunction "1_1") (pintype "unspecified"))
      (node (ref "R2") (pin "1") (pinfunction "1_1") (pintype "unspecified"))
    )
    (net (code "54") (name "/X_STEP_O") (class "Default")
      (node (ref "P13") (pin "2") (pinfunction "2_2") (pintype "unspecified"))
      (node (ref "U6") (pin "10") (pinfunction "VO6_10") (pintype "unspecified"))
    )
    (net (code "55") (name "/Y_DIR_O") (class "Default")
      (node (ref "P10") (pin "3") (pinfunction "3_3") (pintype "unspecified"))
      (node (ref "P7") (pin "3") (pinfunction "3_3") (pintype "unspecified"))
      (node (ref "U6") (pin "12") (pinfunction "VO4_12") (pintype "unspecified"))
    )
    (net (code "56") (name "/Y_LIMT") (class "Default")
      (node (ref "R4") (pin "2") (pinfunction "2_2") (pintype "unspecified"))
      (node (ref "U7") (pin "5") (pinfunction "IO5_5") (pintype "unspecified"))
    )
    (net (code "57") (name "/Y_LIMT_I") (class "Default")
      (node (ref "D2") (pin "2") (pinfunction "2_2") (pintype "input"))
      (node (ref "P2") (pin "1") (pinfunction "1_1") (pintype "unspecified"))
      (node (ref "R3") (pin "1") (pinfunction "1_1") (pintype "unspecified"))
      (node (ref "R4") (pin "1") (pinfunction "1_1") (pintype "unspecified"))
    )
    (net (code "58") (name "/Y_STEP_O") (class "Default")
      (node (ref "P10") (pin "2") (pinfunction "2_2") (pintype "unspecified"))
      (node (ref "P7") (pin "2") (pinfunction "2_2") (pintype "unspecified"))
      (node (ref "U6") (pin "11") (pinfunction "VO5_11") (pintype "unspecified"))
    )
    (net (code "59") (name "/Z_DIR_O") (class "Default")
      (node (ref "P6") (pin "3") (pinfunction "3_3") (pintype "unspecified"))
      (node (ref "U11") (pin "4") (pinfunction "Y_4") (pintype "unspecified"))
    )
    (net (code "60") (name "/Z_LIMT") (class "Default")
      (node (ref "R7") (pin "2") (pinfunction "2_2") (pintype "unspecified"))
      (node (ref "U7") (pin "4") (pinfunction "IO4_4") (pintype "unspecified"))
    )
    (net (code "61") (name "/Z_LIMT_I") (class "Default")
      (node (ref "D4") (pin "2") (pinfunction "2_2") (pintype "input"))
      (node (ref "P4") (pin "1") (pinfunction "1_1") (pintype "unspecified"))
      (node (ref "R5") (pin "1") (pinfunction "1_1") (pintype "unspecified"))
      (node (ref "R7") (pin "1") (pinfunction "1_1") (pintype "unspecified"))
    )
    (net (code "62") (name "/Z_STEP_O") (class "Default")
      (node (ref "P6") (pin "2") (pinfunction "2_2") (pintype "unspecified"))
      (node (ref "U6") (pin "13") (pinfunction "VO3_13") (pintype "unspecified"))
    )
    (net (code "63") (name "3V3") (class "Default")
      (node (ref "C6") (pin "2") (pinfunction "2_2") (pintype "input"))
      (node (ref "C7") (pin "2") (pinfunction "2_2") (pintype "input"))
      (node (ref "C8") (pin "2") (pinfunction "2_2") (pintype "unspecified"))
      (node (ref "D10") (pin "2") (pinfunction "2_2") (pintype "input"))
      (node (ref "R12") (pin "2") (pinfunction "2_2") (pintype "unspecified"))
      (node (ref "R14") (pin "1") (pinfunction "1_1") (pintype "unspecified"))
      (node (ref "R16") (pin "1") (pinfunction "1_1") (pintype "unspecified"))
      (node (ref "R31") (pin "1") (pinfunction "1_1") (pintype "unspecified"))
      (node (ref "R33") (pin "2") (pinfunction "2_2") (pintype "unspecified"))
      (node (ref "U2") (pin "2") (pinfunction "OUT_2") (pintype "unspecified"))
      (node (ref "U2") (pin "4") (pinfunction "=_4") (pintype "unspecified"))
      (node (ref "U6") (pin "1") (pinfunction "VDDA_1") (pintype "unspecified"))
      (node (ref "U7") (pin "2") (pinfunction "3V3_2") (pintype "unspecified"))
    )
    (net (code "64") (name "5V_VCC") (class "Default")
      (node (ref "C14") (pin "2") (pinfunction "2_2") (pintype "unspecified"))
      (node (ref "C15") (pin "2") (pinfunction "2_2") (pintype "unspecified"))
      (node (ref "C16") (pin "2") (pinfunction "2_2") (pintype "unspecified"))
      (node (ref "C17") (pin "2") (pinfunction "2_2") (pintype "unspecified"))
      (node (ref "C18") (pin "2") (pinfunction "2_2") (pintype "unspecified"))
      (node (ref "C19") (pin "2") (pinfunction "2_2") (pintype "unspecified"))
      (node (ref "C20") (pin "1") (pinfunction "1_1") (pintype "unspecified"))
      (node (ref "C21") (pin "2") (pinfunction "2_2") (pintype "unspecified"))
      (node (ref "C22") (pin "1") (pinfunction "1_1") (pintype "unspecified"))
      (node (ref "C23") (pin "1") (pinfunction "1_1") (pintype "unspecified"))
      (node (ref "C27") (pin "1") (pinfunction "1_1") (pintype "input"))
      (node (ref "C3") (pin "1") (pinfunction "1_1") (pintype "input"))
      (node (ref "C4") (pin "2") (pinfunction "2_2") (pintype "unspecified"))
      (node (ref "C5") (pin "1") (pinfunction "1_1") (pintype "input"))
      (node (ref "D13") (pin "1") (pinfunction "c_1") (pintype "input"))
      (node (ref "D8") (pin "2") (pinfunction "2_2") (pintype "input"))
      (node (ref "H1") (pin "5") (pinfunction "5_5") (pintype "unspecified"))
      (node (ref "H1") (pin "6") (pinfunction "6_6") (pintype "unspecified"))
      (node (ref "H1") (pin "7") (pinfunction "7_7") (pintype "unspecified"))
      (node (ref "H2") (pin "2") (pinfunction "2_2") (pintype "unspecified"))
      (node (ref "L1") (pin "1") (pinfunction "1_1") (pintype "unspecified"))
      (node (ref "P1") (pin "3") (pinfunction "3_3") (pintype "unspecified"))
      (node (ref "P10") (pin "4") (pinfunction "4_4") (pintype "unspecified"))
      (node (ref "P13") (pin "4") (pinfunction "4_4") (pintype "unspecified"))
      (node (ref "P14") (pin "4") (pinfunction "4_4") (pintype "unspecified"))
      (node (ref "P16") (pin "1") (pinfunction "1_1") (pintype "unspecified"))
      (node (ref "P18") (pin "1") (pinfunction "1_1") (pintype "unspecified"))
      (node (ref "P2") (pin "3") (pinfunction "3_3") (pintype "unspecified"))
      (node (ref "P4") (pin "3") (pinfunction "3_3") (pintype "unspecified"))
      (node (ref "P5") (pin "3") (pinfunction "3_3") (pintype "unspecified"))
      (node (ref "P6") (pin "4") (pinfunction "4_4") (pintype "unspecified"))
      (node (ref "P7") (pin "4") (pinfunction "4_4") (pintype "unspecified"))
      (node (ref "P9") (pin "1") (pinfunction "1_1") (pintype "unspecified"))
      (node (ref "R1") (pin "2") (pinfunction "2_2") (pintype "unspecified"))
      (node (ref "R10") (pin "2") (pinfunction "2_2") (pintype "unspecified"))
      (node (ref "R17") (pin "1") (pinfunction "1_1") (pintype "unspecified"))
      (node (ref "R23") (pin "1") (pinfunction "1_1") (pintype "unspecified"))
      (node (ref "R24") (pin "1") (pinfunction "1_1") (pintype "unspecified"))
      (node (ref "R25") (pin "1") (pinfunction "1_1") (pintype "unspecified"))
      (node (ref "R3") (pin "2") (pinfunction "2_2") (pintype "unspecified"))
      (node (ref "R37") (pin "2") (pinfunction "2_2") (pintype "input"))
      (node (ref "R38") (pin "2") (pinfunction "2_2") (pintype "input"))
      (node (ref "R46") (pin "2") (pinfunction "2_2") (pintype "unspecified"))
      (node (ref "R49") (pin "2") (pinfunction "2_2") (pintype "unspecified"))
      (node (ref "R5") (pin "2") (pinfunction "2_2") (pintype "unspecified"))
      (node (ref "R6") (pin "2") (pinfunction "2_2") (pintype "unspecified"))
      (node (ref "U1") (pin "3") (pinfunction "FB_3") (pintype "input"))
      (node (ref "U10") (pin "5") (pinfunction "VCC_5") (pintype "unspecified"))
      (node (ref "U11") (pin "5") (pinfunction "VCC_5") (pintype "unspecified"))
      (node (ref "U12") (pin "5") (pinfunction "VCC_5") (pintype "unspecified"))
      (node (ref "U13") (pin "5") (pinfunction "VCC_5") (pintype "unspecified"))
      (node (ref "U14") (pin "5") (pinfunction "VBUS_5") (pintype "unspecified"))
      (node (ref "U15") (pin "16") (pinfunction "VCC_16") (pintype "unspecified"))
      (node (ref "U2") (pin "3") (pinfunction "IN_3") (pintype "unspecified"))
      (node (ref "U4") (pin "5") (pinfunction "VCC_5") (pintype "unspecified"))
      (node (ref "U5") (pin "5") (pinfunction "VCC_5") (pintype "unspecified"))
      (node (ref "U6") (pin "16") (pinfunction "VDDB_16") (pintype "unspecified"))
      (node (ref "U8") (pin "5") (pinfunction "VCC_5") (pintype "unspecified"))
      (node (ref "U9") (pin "5") (pinfunction "VCC_5") (pintype "unspecified"))
      (node (ref "USB1") (pin "1") (pinfunction "VCC_1") (pintype "input"))
    )
    (net (code "65") (name "24V") (class "Default")
      (node (ref "C9") (pin "1") (pintype "unspecified"))
      (node (ref "D3") (pin "1") (pinfunction "1_1") (pintype "unspecified"))
      (node (ref "P15") (pin "1") (pinfunction "1_1") (pintype "unspecified"))
      (node (ref "P3") (pin "2") (pinfunction "2_2") (pintype "input"))
      (node (ref "R9") (pin "2") (pinfunction "2_2") (pintype "unspecified"))
      (node (ref "U3") (pin "1") (pinfunction "IN_1") (pintype "unspecified"))
    )
    (net (code "66") (name "GND") (class "Default")
      (node (ref "C1") (pin "2") (pintype "unspecified"))
      (node (ref "C10") (pin "2") (pintype "unspecified"))
      (node (ref "C11") (pin "1") (pinfunction "1_1") (pintype "unspecified"))
      (node (ref "C12") (pin "1") (pinfunction "1_1") (pintype "unspecified"))
      (node (ref "C13") (pin "1") (pinfunction "1_1") (pintype "unspecified"))
      (node (ref "C14") (pin "1") (pinfunction "1_1") (pintype "unspecified"))
      (node (ref "C15") (pin "1") (pinfunction "1_1") (pintype "unspecified"))
      (node (ref "C16") (pin "1") (pinfunction "1_1") (pintype "unspecified"))
      (node (ref "C17") (pin "1") (pinfunction "1_1") (pintype "unspecified"))
      (node (ref "C18") (pin "1") (pinfunction "1_1") (pintype "unspecified"))
      (node (ref "C19") (pin "1") (pinfunction "1_1") (pintype "unspecified"))
      (node (ref "C2") (pin "1") (pinfunction "1_1") (pintype "unspecified"))
      (node (ref "C20") (pin "2") (pinfunction "2_2") (pintype "unspecified"))
      (node (ref "C21") (pin "1") (pinfunction "1_1") (pintype "unspecified"))
      (node (ref "C22") (pin "2") (pinfunction "2_2") (pintype "unspecified"))
      (node (ref "C23") (pin "2") (pinfunction "2_2") (pintype "unspecified"))
      (node (ref "C24") (pin "2") (pinfunction "2_2") (pintype "unspecified"))
      (node (ref "C25") (pin "2") (pinfunction "2_2") (pintype "unspecified"))
      (node (ref "C26") (pin "2") (pinfunction "2_2") (pintype "unspecified"))
      (node (ref "C27") (pin "2") (pinfunction "2_2") (pintype "input"))
      (node (ref "C3") (pin "2") (pinfunction "2_2") (pintype "input"))
      (node (ref "C4") (pin "1") (pinfunction "1_1") (pintype "unspecified"))
      (node (ref "C5") (pin "2") (pinfunction "2_2") (pintype "input"))
      (node (ref "C6") (pin "1") (pinfunction "1_1") (pintype "input"))
      (node (ref "C7") (pin "1") (pinfunction "1_1") (pintype "input"))
      (node (ref "C8") (pin "1") (pinfunction "1_1") (pintype "unspecified"))
      (node (ref "C9") (pin "2") (pintype "unspecified"))
      (node (ref "D1") (pin "1") (pinfunction "1_1") (pintype "input"))
      (node (ref "D10") (pin "1") (pinfunction "1_1") (pintype "input"))
      (node (ref "D11") (pin "2") (pinfunction "2_2") (pintype "unspecified"))
      (node (ref "D2") (pin "1") (pinfunction "1_1") (pintype "input"))
      (node (ref "D4") (pin "1") (pinfunction "1_1") (pintype "input"))
      (node (ref "D5") (pin "1") (pinfunction "1_1") (pintype "input"))
      (node (ref "D6") (pin "1") (pinfunction "1_1") (pintype "input"))
      (node (ref "D7") (pin "2") (pinfunction "2_2") (pintype "unspecified"))
      (node (ref "D8") (pin "1") (pinfunction "1_1") (pintype "input"))
      (node (ref "D9") (pin "2") (pinfunction "2_2") (pintype "unspecified"))
      (node (ref "H2") (pin "1") (pinfunction "1_1") (pintype "unspecified"))
      (node (ref "H2") (pin "7") (pinfunction "7_7") (pintype "unspecified"))
      (node (ref "K1") (pin "1") (pinfunction "1_1") (pintype "unspecified"))
      (node (ref "K1") (pin "2") (pinfunction "2_2") (pintype "unspecified"))
      (node (ref "P1") (pin "2") (pinfunction "2_2") (pintype "unspecified"))
      (node (ref "P11") (pin "2") (pintype "input"))
      (node (ref "P12") (pin "2") (pintype "input"))
      (node (ref "P15") (pin "3") (pinfunction "3_3") (pintype "unspecified"))
      (node (ref "P16") (pin "3") (pinfunction "3_3") (pintype "unspecified"))
      (node (ref "P17") (pin "4") (pinfunction "GND_4") (pintype "unspecified"))
      (node (ref "P17") (pin "5") (pinfunction "GND_5") (pintype "unspecified"))
      (node (ref "P17") (pin "6") (pinfunction "GND_6") (pintype "unspecified"))
      (node (ref "P18") (pin "4") (pinfunction "4_4") (pintype "unspecified"))
      (node (ref "P2") (pin "2") (pinfunction "2_2") (pintype "unspecified"))
      (node (ref "P3") (pin "1") (pinfunction "1_1") (pintype "input"))
      (node (ref "P4") (pin "2") (pinfunction "2_2") (pintype "unspecified"))
      (node (ref "P5") (pin "2") (pinfunction "2_2") (pintype "unspecified"))
      (node (ref "P9") (pin "3") (pinfunction "3_3") (pintype "unspecified"))
      (node (ref "Q1") (pin "2") (pinfunction "E_2") (pintype "input"))
      (node (ref "R11") (pin "2") (pinfunction "2_2") (pintype "unspecified"))
      (node (ref "R13") (pin "2") (pinfunction "2_2") (pintype "unspecified"))
      (node (ref "R15") (pin "2") (pinfunction "2_2") (pintype "unspecified"))
      (node (ref "R18") (pin "2") (pinfunction "2_2") (pintype "unspecified"))
      (node (ref "R19") (pin "2") (pinfunction "2_2") (pintype "unspecified"))
      (node (ref "R23") (pin "2") (pinfunction "2_2") (pintype "unspecified"))
      (node (ref "R24") (pin "2") (pinfunction "2_2") (pintype "unspecified"))
      (node (ref "R25") (pin "2") (pinfunction "2_2") (pintype "unspecified"))
      (node (ref "R26") (pin "2") (pinfunction "2_2") (pintype "input"))
      (node (ref "R27") (pin "2") (pinfunction "2_2") (pintype "input"))
      (node (ref "R29") (pin "2") (pinfunction "2_2") (pintype "input"))
      (node (ref "R34") (pin "2") (pinfunction "2_2") (pintype "input"))
      (node (ref "R35") (pin "2") (pinfunction "2_2") (pintype "input"))
      (node (ref "R36") (pin "2") (pinfunction "2_2") (pintype "input"))
      (node (ref "R39") (pin "2") (pinfunction "2_2") (pintype "input"))
      (node (ref "U1") (pin "5") (pinfunction "GND_5") (pintype "input"))
      (node (ref "U1") (pin "6") (pinfunction "GND_6") (pintype "input"))
      (node (ref "U1") (pin "7") (pinfunction "GND_7") (pintype "input"))
      (node (ref "U1") (pin "8") (pinfunction "GND_8") (pintype "input"))
      (node (ref "U10") (pin "3") (pinfunction "GND_3") (pintype "unspecified"))
      (node (ref "U11") (pin "3") (pinfunction "GND_3") (pintype "unspecified"))
      (node (ref "U12") (pin "3") (pinfunction "GND_3") (pintype "unspecified"))
      (node (ref "U13") (pin "3") (pinfunction "GND_3") (pintype "unspecified"))
      (node (ref "U14") (pin "2") (pinfunction "GND_2") (pintype "unspecified"))
      (node (ref "U15") (pin "1") (pinfunction "GND_1") (pintype "unspecified"))
      (node (ref "U16") (pin "2") (pinfunction "2_2") (pintype "unspecified"))
      (node (ref "U2") (pin "1") (pinfunction "GND_1") (pintype "unspecified"))
      (node (ref "U3") (pin "2") (pinfunction "TAB_2") (pintype "unspecified"))
      (node (ref "U4") (pin "3") (pinfunction "GND_3") (pintype "unspecified"))
      (node (ref "U5") (pin "3") (pinfunction "GND_3") (pintype "unspecified"))
      (node (ref "U6") (pin "8") (pinfunction "GNDA_8") (pintype "unspecified"))
      (node (ref "U6") (pin "9") (pinfunction "GNDB_9") (pintype "unspecified"))
      (node (ref "U7") (pin "1") (pinfunction "GND_1") (pintype "unspecified"))
      (node (ref "U7") (pin "40") (pinfunction "GND_40") (pintype "unspecified"))
      (node (ref "U7") (pin "41") (pinfunction "GND_41") (pintype "unspecified"))
      (node (ref "U8") (pin "3") (pinfunction "GND_3") (pintype "unspecified"))
      (node (ref "U9") (pin "3") (pinfunction "GND_3") (pintype "unspecified"))
      (node (ref "USB1") (pin "4") (pinfunction "GND_4") (pintype "input"))
      (node (ref "USB1") (pin "5") (pinfunction "SHLD_5") (pintype "unspecified"))
    )
    (net (code "67") (name "Net-(C11-Pad2)") (class "Default")
      (node (ref "C11") (pin "2") (pinfunction "2_2") (pintype "unspecified"))
      (node (ref "P11") (pin "1") (pintype "input"))
      (node (ref "R16") (pin "2") (pinfunction "2_2") (pintype "unspecified"))
      (node (ref "R20") (pin "2") (pinfunction "2_2") (pintype "input"))
    )
    (net (code "68") (name "Net-(C12-Pad2)") (class "Default")
      (node (ref "C12") (pin "2") (pinfunction "2_2") (pintype "unspecified"))
      (node (ref "K1") (pin "3") (pinfunction "3_3") (pintype "unspecified"))
      (node (ref "K1") (pin "4") (pinfunction "4_4") (pintype "unspecified"))
      (node (ref "P12") (pin "1") (pintype "input"))
      (node (ref "R14") (pin "2") (pinfunction "2_2") (pintype "unspecified"))
      (node (ref "R21") (pin "2") (pinfunction "2_2") (pintype "input"))
    )
    (net (code "69") (name "Net-(C13-Pad2)") (class "Default")
      (node (ref "C13") (pin "2") (pinfunction "2_2") (pintype "unspecified"))
      (node (ref "P9") (pin "2") (pinfunction "2_2") (pintype "unspecified"))
      (node (ref "R17") (pin "2") (pinfunction "2_2") (pintype "unspecified"))
      (node (ref "R22") (pin "2") (pinfunction "2_2") (pintype "input"))
    )
    (net (code "70") (name "Net-(D7-Pad1)") (class "Default")
      (node (ref "D7") (pin "1") (pinfunction "1_1") (pintype "unspecified"))
      (node (ref "R9") (pin "1") (pinfunction "1_1") (pintype "unspecified"))
    )
    (net (code "71") (name "Net-(D9-Pad1)") (class "Default")
      (node (ref "D9") (pin "1") (pinfunction "1_1") (pintype "unspecified"))
      (node (ref "R10") (pin "1") (pinfunction "1_1") (pintype "unspecified"))
    )
    (net (code "72") (name "Net-(D11-Pad1)") (class "Default")
      (node (ref "D11") (pin "1") (pinfunction "1_1") (pintype "unspecified"))
      (node (ref "R12") (pin "1") (pinfunction "1_1") (pintype "unspecified"))
    )
    (net (code "73") (name "Net-(D12-c)") (class "Default")
      (node (ref "D12") (pin "1") (pinfunction "c_1") (pintype "input"))
      (node (ref "U15") (pin "2") (pinfunction "TXD_2") (pintype "unspecified"))
    )
    (net (code "74") (name "Net-(D14-A)") (class "Default")
      (node (ref "D14") (pin "2") (pinfunction "A_2") (pintype "input"))
      (node (ref "R46") (pin "1") (pinfunction "1_1") (pintype "unspecified"))
      (node (ref "U15") (pin "3") (pinfunction "RXD_3") (pintype "unspecified"))
    )
    (net (code "75") (name "Net-(D15-A)") (class "Default")
      (node (ref "D15") (pin "2") (pinfunction "A_2") (pintype "input"))
      (node (ref "P18") (pin "3") (pinfunction "3_3") (pintype "unspecified"))
      (node (ref "R49") (pin "1") (pinfunction "1_1") (pintype "unspecified"))
    )
    (net (code "76") (name "Net-(D15-c)") (class "Default")
      (node (ref "D15") (pin "1") (pinfunction "c_1") (pintype "input"))
      (node (ref "R48") (pin "1") (pinfunction "1_1") (pintype "input"))
      (node (ref "R50") (pin "2") (pinfunction "2_2") (pintype "input"))
    )
    (net (code "77") (name "Net-(D16-A)") (class "Default")
      (node (ref "D16") (pin "2") (pinfunction "A_2") (pintype "input"))
      (node (ref "R51") (pin "2") (pinfunction "2_2") (pintype "input"))
      (node (ref "R53") (pin "2") (pinfunction "2_2") (pintype "input"))
    )
    (net (code "78") (name "Net-(D16-c)") (class "Default")
      (node (ref "D16") (pin "1") (pinfunction "c_1") (pintype "input"))
      (node (ref "P18") (pin "2") (pinfunction "2_2") (pintype "unspecified"))
    )
    (net (code "79") (name "Net-(H1-Pad3)") (class "Default")
      (node (ref "H1") (pin "3") (pinfunction "3_3") (pintype "unspecified"))
      (node (ref "H1") (pin "4") (pinfunction "4_4") (pintype "unspecified"))
    )
    (net (code "80") (name "Net-(Q1-B)") (class "Default")
      (node (ref "Q1") (pin "1") (pinfunction "B_1") (pintype "input"))
      (node (ref "R38") (pin "1") (pinfunction "1_1") (pintype "input"))
      (node (ref "R40") (pin "2") (pinfunction "2_2") (pintype "input"))
    )
    (net (code "81") (name "Net-(Q2-B)") (class "Default")
      (node (ref "Q2") (pin "1") (pinfunction "B_1") (pintype "unspecified"))
      (node (ref "R47") (pin "2") (pinfunction "2_2") (pintype "unspecified"))
    )
    (net (code "82") (name "Net-(Q2-E)") (class "Default")
      (node (ref "Q2") (pin "2") (pinfunction "E_2") (pintype "unspecified"))
      (node (ref "R52") (pin "1") (pinfunction "1_1") (pintype "unspecified"))
      (node (ref "U15") (pin "13") (pinfunction "DTR#_13") (pintype "unspecified"))
    )
    (net (code "83") (name "Net-(Q3-B)") (class "Default")
      (node (ref "Q3") (pin "1") (pinfunction "B_1") (pintype "unspecified"))
      (node (ref "R52") (pin "2") (pinfunction "2_2") (pintype "unspecified"))
    )
    (net (code "84") (name "Net-(Q3-E)") (class "Default")
      (node (ref "Q3") (pin "2") (pinfunction "E_2") (pintype "unspecified"))
      (node (ref "R47") (pin "1") (pinfunction "1_1") (pintype "unspecified"))
      (node (ref "U15") (pin "14") (pinfunction "RTS#_14") (pintype "unspecified"))
    )
    (net (code "85") (name "Net-(U1-ON{slash}OFF)") (class "Default")
      (node (ref "R11") (pin "1") (pinfunction "1_1") (pintype "unspecified"))
      (node (ref "U1") (pin "4") (pinfunction "ON/OFF_4") (pintype "input"))
    )
    (net (code "86") (name "Net-(U1-OUTPUT)") (class "Default")
      (node (ref "D6") (pin "2") (pinfunction "2_2") (pintype "input"))
      (node (ref "L1") (pin "2") (pinfunction "2_2") (pintype "unspecified"))
      (node (ref "U1") (pin "2") (pinfunction "OUTPUT_2") (pintype "input"))
    )
    (net (code "87") (name "Net-(U7-IO1)") (class "Default")
      (node (ref "R28") (pin "2") (pinfunction "2_2") (pintype "input"))
      (node (ref "U7") (pin "39") (pinfunction "IO1_39") (pintype "unspecified"))
    )
    (net (code "88") (name "Net-(U7-IO10)") (class "Default")
      (node (ref "R41") (pin "2") (pinfunction "2_2") (pintype "input"))
      (node (ref "U7") (pin "18") (pinfunction "IO10_18") (pintype "unspecified"))
    )
    (net (code "89") (name "Net-(U7-IO11)") (class "Default")
      (node (ref "R42") (pin "2") (pinfunction "2_2") (pintype "input"))
      (node (ref "U7") (pin "19") (pinfunction "IO11_19") (pintype "unspecified"))
    )
    (net (code "90") (name "Net-(U7-IO41)") (class "Default")
      (node (ref "R32") (pin "2") (pinfunction "2_2") (pintype "input"))
      (node (ref "U7") (pin "34") (pinfunction "IO41_34") (pintype "unspecified"))
    )
    (net (code "91") (name "Net-(U7-IO42)") (class "Default")
      (node (ref "R30") (pin "2") (pinfunction "2_2") (pintype "input"))
      (node (ref "U7") (pin "35") (pinfunction "IO42_35") (pintype "unspecified"))
    )
    (net (code "92") (name "Net-(U7-IO45)") (class "Default")
      (node (ref "R44") (pin "2") (pinfunction "2_2") (pintype "input"))
      (node (ref "U7") (pin "26") (pinfunction "IO45_26") (pintype "unspecified"))
    )
    (net (code "93") (name "Net-(U7-IO47)") (class "Default")
      (node (ref "R43") (pin "2") (pinfunction "2_2") (pintype "input"))
      (node (ref "U7") (pin "24") (pinfunction "IO47_24") (pintype "unspecified"))
    )
    (net (code "94") (name "Net-(U15-UD+)") (class "Default")
      (node (ref "U15") (pin "5") (pinfunction "UD+_5") (pintype "unspecified"))
      (node (ref "U16") (pin "6") (pinfunction "6_6") (pintype "unspecified"))
    )
    (net (code "95") (name "Net-(U15-UD-)") (class "Default")
      (node (ref "U15") (pin "6") (pinfunction "UD-_6") (pintype "unspecified"))
      (node (ref "U16") (pin "4") (pinfunction "4_4") (pintype "unspecified"))
    )
    (net (code "96") (name "Net-(U15-V3)") (class "Default")
      (node (ref "C24") (pin "1") (pinfunction "1_1") (pintype "unspecified"))
      (node (ref "U15") (pin "4") (pinfunction "V3_4") (pintype "unspecified"))
    )
    (net (code "97") (name "Net-(U15-XI)") (class "Default")
      (node (ref "C25") (pin "1") (pinfunction "1_1") (pintype "unspecified"))
      (node (ref "U15") (pin "7") (pinfunction "XI_7") (pintype "unspecified"))
      (node (ref "Y1") (pin "2") (pinfunction "OSC2_2") (pintype "unspecified"))
    )
    (net (code "98") (name "Net-(U15-XO)") (class "Default")
      (node (ref "C26") (pin "1") (pinfunction "1_1") (pintype "unspecified"))
      (node (ref "U15") (pin "8") (pinfunction "XO_8") (pintype "unspecified"))
      (node (ref "Y1") (pin "1") (pinfunction "OSC1_1") (pintype "unspecified"))
    )
    (net (code "99") (name "VIN_24V") (class "Default")
      (node (ref "C1") (pin "1") (pintype "unspecified"))
      (node (ref "C2") (pin "2") (pinfunction "2_2") (pintype "unspecified"))
      (node (ref "D3") (pin "2") (pinfunction "2_2") (pintype "unspecified"))
      (node (ref "U1") (pin "1") (pinfunction "VIN_1") (pintype "input"))
    )
    (net (code "100") (name "VUSB") (class "Default")
      (node (ref "D13") (pin "2") (pinfunction "A_2") (pintype "input"))
      (node (ref "P17") (pin "1") (pinfunction "VBUS_1") (pintype "unspecified"))
      (node (ref "U16") (pin "5") (pinfunction "5_5") (pintype "unspecified"))
    )
    (net (code "101") (name "unconnected-(U4-NC-Pad1)") (class "Default")
      (node (ref "U4") (pin "1") (pinfunction "NC_1") (pintype "unspecified"))
    )
    (net (code "102") (name "unconnected-(U5-NC-Pad1)") (class "Default")
      (node (ref "U5") (pin "1") (pinfunction "NC_1") (pintype "unspecified"))
    )
    (net (code "103") (name "unconnected-(U7-IO35-Pad28)") (class "Default")
      (node (ref "U7") (pin "28") (pinfunction "IO35_28") (pintype "unspecified+no_connect"))
    )
    (net (code "104") (name "unconnected-(U7-IO36-Pad29)") (class "Default")
      (node (ref "U7") (pin "29") (pinfunction "IO36_29") (pintype "unspecified+no_connect"))
    )
    (net (code "105") (name "unconnected-(U7-IO37-Pad30)") (class "Default")
      (node (ref "U7") (pin "30") (pinfunction "IO37_30") (pintype "unspecified+no_connect"))
    )
    (net (code "106") (name "unconnected-(U8-NC-Pad1)") (class "Default")
      (node (ref "U8") (pin "1") (pinfunction "NC_1") (pintype "unspecified"))
    )
    (net (code "107") (name "unconnected-(U9-NC-Pad1)") (class "Default")
      (node (ref "U9") (pin "1") (pinfunction "NC_1") (pintype "unspecified"))
    )
    (net (code "108") (name "unconnected-(U10-NC-Pad1)") (class "Default")
      (node (ref "U10") (pin "1") (pinfunction "NC_1") (pintype "unspecified"))
    )
    (net (code "109") (name "unconnected-(U11-NC-Pad1)") (class "Default")
      (node (ref "U11") (pin "1") (pinfunction "NC_1") (pintype "unspecified"))
    )
    (net (code "110") (name "unconnected-(U12-NC-Pad1)") (class "Default")
      (node (ref "U12") (pin "1") (pinfunction "NC_1") (pintype "unspecified"))
    )
    (net (code "111") (name "unconnected-(U13-NC-Pad1)") (class "Default")
      (node (ref "U13") (pin "1") (pinfunction "NC_1") (pintype "unspecified"))
    )
    (net (code "112") (name "unconnected-(U15-CTS#-Pad9)") (class "Default")
      (node (ref "U15") (pin "9") (pinfunction "CTS#_9") (pintype "unspecified"))
    )
    (net (code "113") (name "unconnected-(U15-DCD#-Pad12)") (class "Default")
      (node (ref "U15") (pin "12") (pinfunction "DCD#_12") (pintype "unspecified"))
    )
    (net (code "114") (name "unconnected-(U15-DSR#-Pad10)") (class "Default")
      (node (ref "U15") (pin "10") (pinfunction "DSR#_10") (pintype "unspecified"))
    )
    (net (code "115") (name "unconnected-(U15-R232-Pad15)") (class "Default")
      (node (ref "U15") (pin "15") (pinfunction "R232_15") (pintype "unspecified"))
    )
    (net (code "116") (name "unconnected-(U15-RI#-Pad11)") (class "Default")
      (node (ref "U15") (pin "11") (pinfunction "RI#_11") (pintype "unspecified"))
    )
  )
)
